# BandpassedGainAmpThruholeMounthole.net
KiCad netlist of a schematic drawn in EAGLE
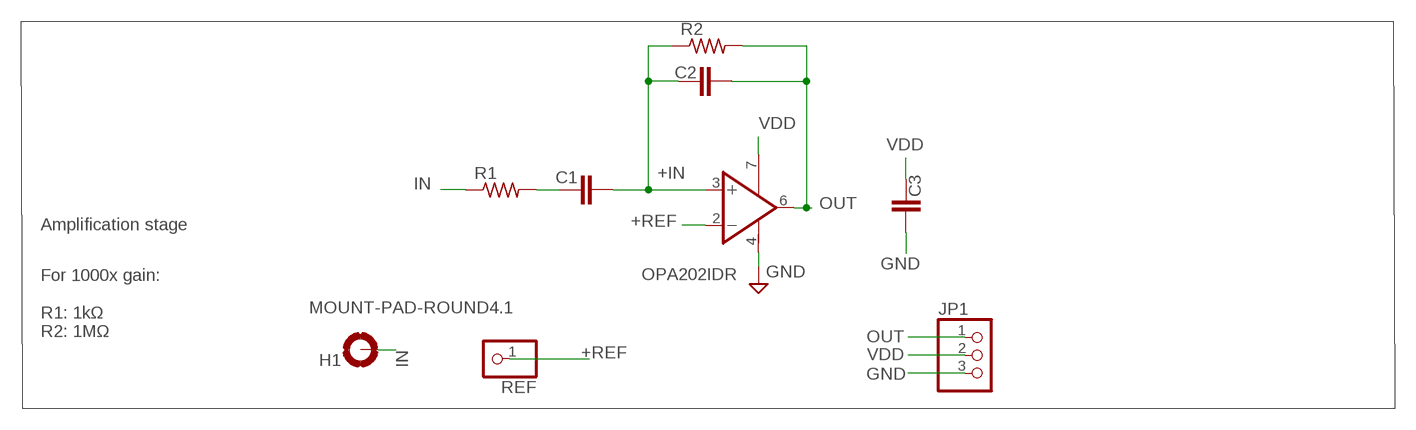
[diagram p0: schematic, sheet 1]

(export (version "E")
  (design (tool "Eeschema 10.0.6"))
  (components
    (comp (ref "C1")
      (value "C2.5/2")
      (footprint "eagle-import:C2.5-2")
      (libsource (lib "eagle-import") (part "C2.5/2"))
    )
    (comp (ref "C2")
      (value "C2.5/2")
      (footprint "eagle-import:C2.5-2")
      (libsource (lib "eagle-import") (part "C2.5/2"))
    )
    (comp (ref "C3")
      (value "C2.5/2")
      (footprint "eagle-import:C2.5-2")
      (libsource (lib "eagle-import") (part "C2.5/2"))
    )
    (comp (ref "H1")
      (value "MOUNT-PAD-ROUND4.1")
      (footprint "eagle-import:4,1-PAD")
      (libsource (lib "eagle-import") (part "MOUNT-PAD-ROUND4.1"))
    )
    (comp (ref "JP1")
      (value "PINHD-1X3")
      (footprint "eagle-import:1X03")
      (libsource (lib "eagle-import") (part "PINHD-1X3"))
    )
    (comp (ref "R1")
      (value "R-US_0204/5")
      (footprint "eagle-import:0204_5")
      (libsource (lib "eagle-import") (part "R-US_0204/5"))
    )
    (comp (ref "R2")
      (value "R-US_0204/5")
      (footprint "eagle-import:0204_5")
      (libsource (lib "eagle-import") (part "R-US_0204/5"))
    )
    (comp (ref "REF")
      (value "PINHD-1X1")
      (footprint "eagle-import:1X01")
      (libsource (lib "eagle-import") (part "PINHD-1X1"))
    )
    (comp (ref "U1")
      (value "OPA202IDR")
      (footprint "eagle-import:SOIC127P600X175-8N")
      (fields (field (name "MF") "Texas Instruments"))
      (libsource (lib "eagle-import") (part "OPA202IDR"))
    )
  )
  (nets
    (net (code "1") (name "/+IN") (class "Default")
      (node (ref "C1") (pin "2") (pinfunction "2_2") (pintype "passive"))
      (node (ref "C2") (pin "1") (pinfunction "1_1") (pintype "passive"))
      (node (ref "R2") (pin "1") (pinfunction "1_1") (pintype "passive"))
      (node (ref "U1") (pin "3") (pinfunction "+IN_3") (pintype "input"))
    )
    (net (code "2") (name "/+REF") (class "Default")
      (node (ref "REF") (pin "1") (pinfunction "1_1") (pintype "passive"))
      (node (ref "U1") (pin "2") (pinfunction "-IN_2") (pintype "input"))
    )
    (net (code "3") (name "/IN") (class "Default")
      (node (ref "H1") (pin "B4,1") (pinfunction "MOUNT_B4,1") (pintype "passive"))
      (node (ref "R1") (pin "1") (pinfunction "1_1") (pintype "passive"))
    )
    (net (code "4") (name "/OUT") (class "Default")
      (node (ref "C2") (pin "2") (pinfunction "2_2") (pintype "passive"))
      (node (ref "JP1") (pin "1") (pinfunction "1_1") (pintype "passive"))
      (node (ref "R2") (pin "2") (pinfunction "2_2") (pintype "passive"))
      (node (ref "U1") (pin "6") (pinfunction "OUT_6") (pintype "output"))
    )
    (net (code "5") (name "/VDD") (class "Default")
      (node (ref "C3") (pin "1") (pinfunction "1_1") (pintype "passive"))
      (node (ref "JP1") (pin "2") (pinfunction "2_2") (pintype "passive"))
      (node (ref "U1") (pin "7") (pinfunction "V+_7") (pintype "power_in"))
    )
    (net (code "6") (name "GND") (class "Default")
      (node (ref "C3") (pin "2") (pinfunction "2_2") (pintype "passive"))
      (node (ref "JP1") (pin "3") (pinfunction "3_3") (pintype "passive"))
      (node (ref "U1") (pin "4") (pinfunction "V-_4") (pintype "power_in"))
    )
    (net (code "7") (name "Net-(C1-Pad1)") (class "Default")
      (node (ref "C1") (pin "1") (pinfunction "1_1") (pintype "passive"))
      (node (ref "R1") (pin "2") (pinfunction "2_2") (pintype "passive"))
    )
  )
)
